# OSO-MISC-20-012_Trinket_SWD_Adapter.net
KiCad netlist of a schematic drawn in EAGLE
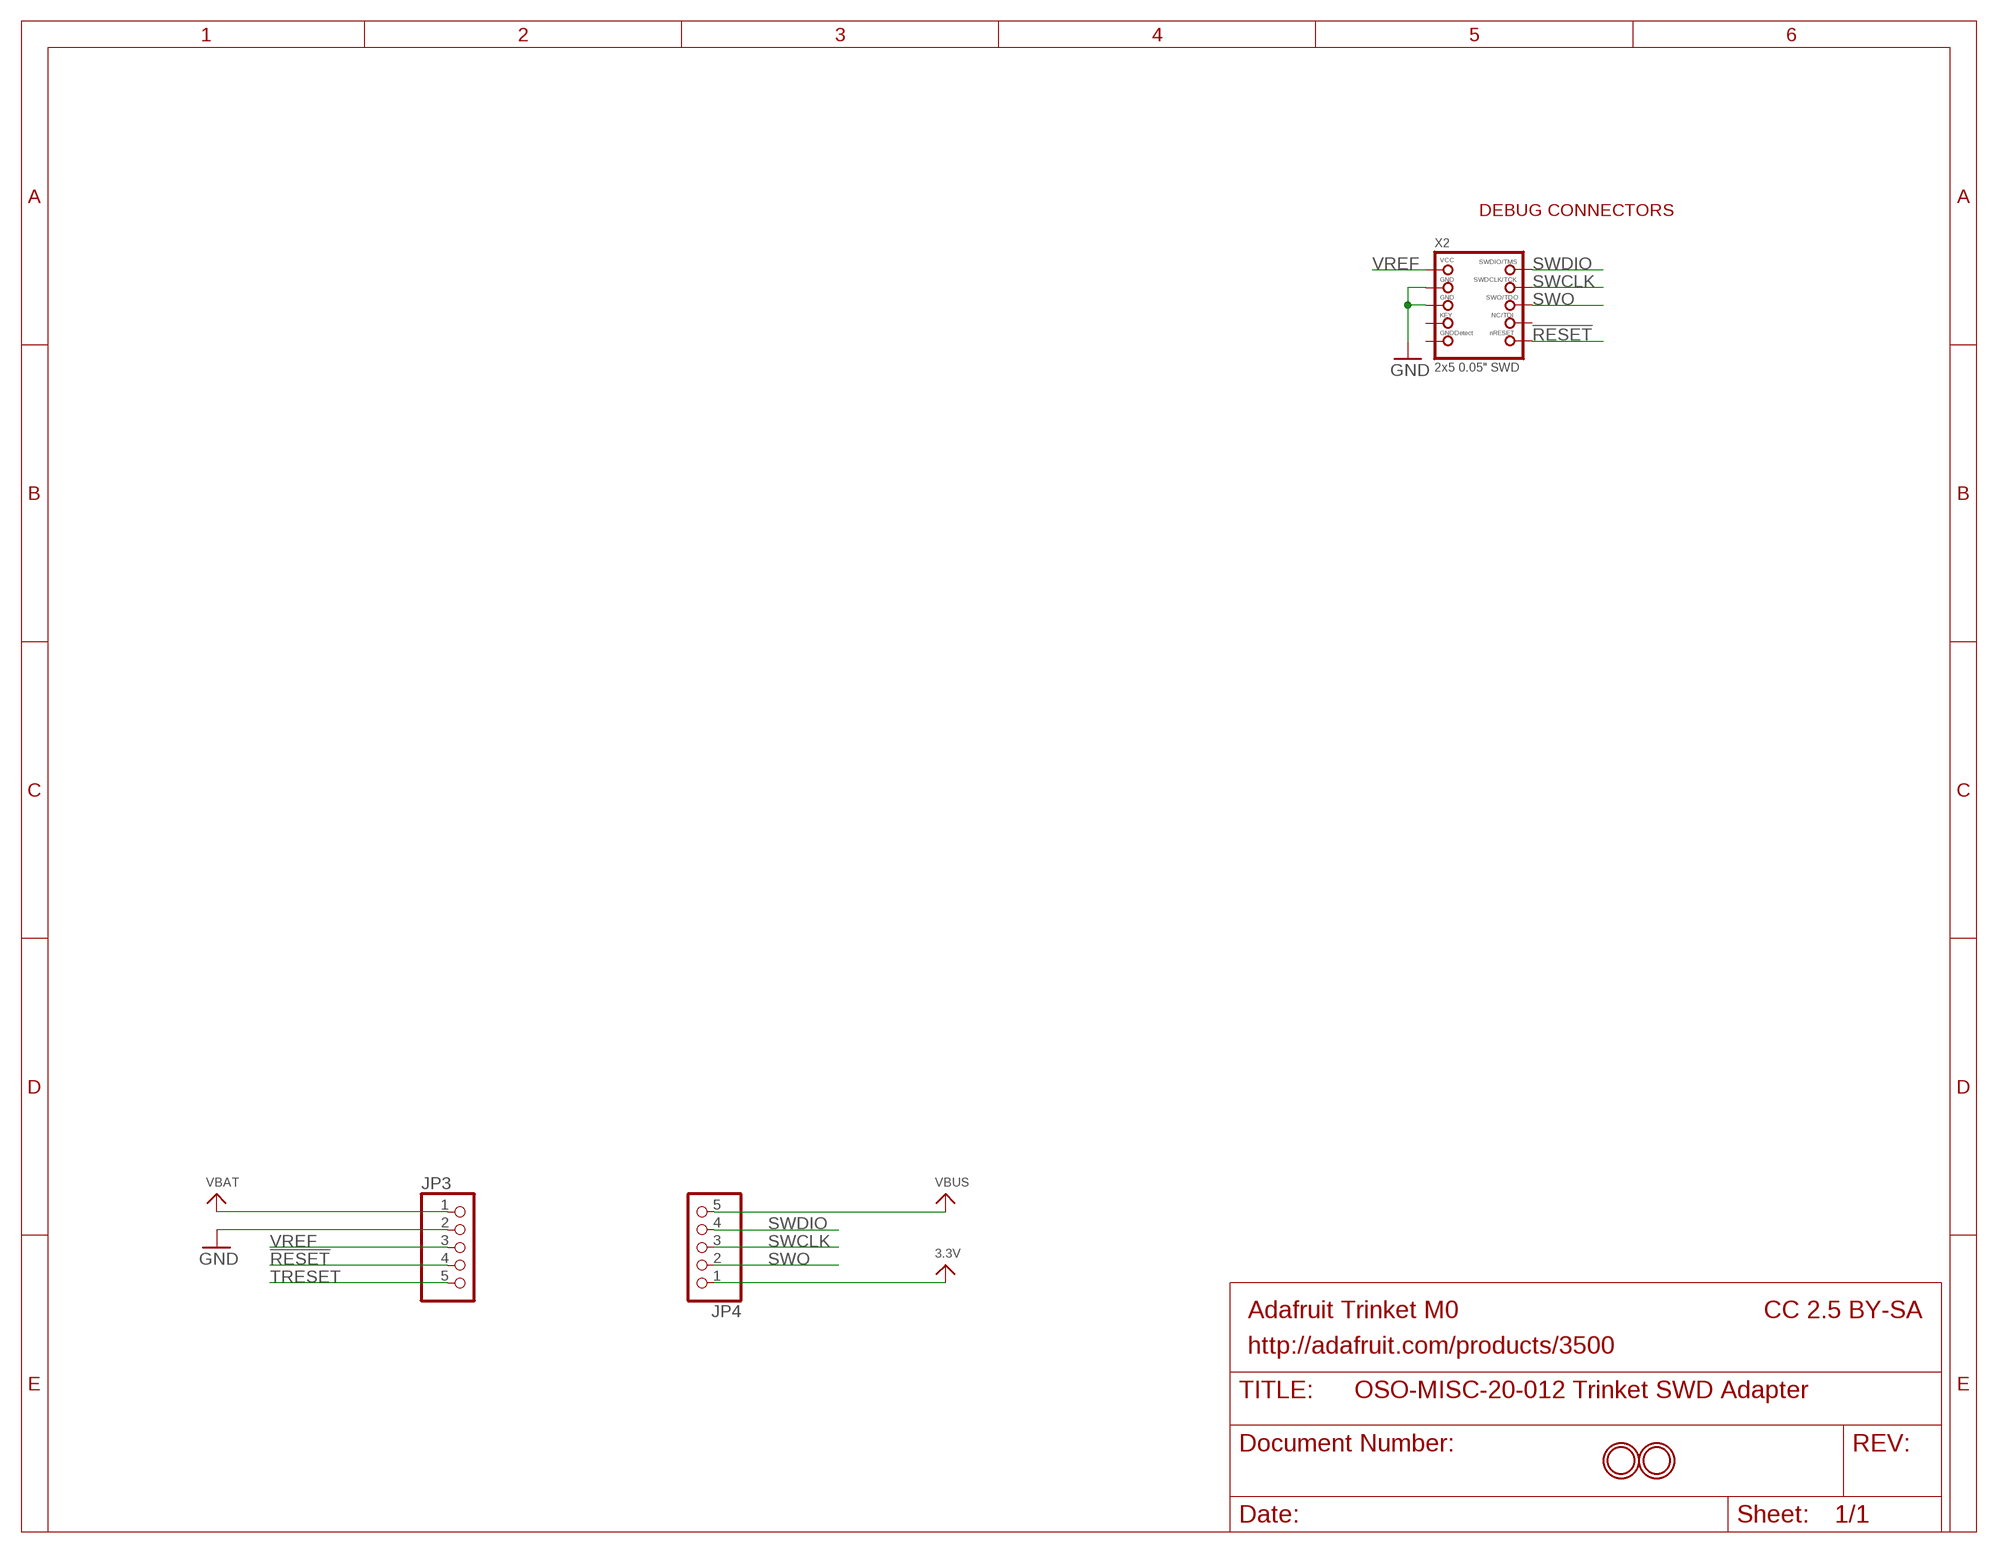
[diagram p0: schematic, sheet 1]

(export (version "E")
  (design (tool "Eeschema 10.0.6"))
  (components
    (comp (ref "JP3")
      (value "HEADER-1X576MIL")
      (footprint "eagle-import:1X05_ROUND_76")
      (libsource (lib "eagle-import") (part "HEADER-1X576MIL"))
    )
    (comp (ref "JP4")
      (value "HEADER-1X576MIL")
      (footprint "eagle-import:1X05_ROUND_76")
      (libsource (lib "eagle-import") (part "HEADER-1X576MIL"))
    )
    (comp (ref "U$8")
      (value "MOUNTINGHOLE2.0")
      (footprint "eagle-import:MOUNTINGHOLE_2.0_PLATED")
      (libsource (lib "eagle-import") (part "MOUNTINGHOLE2.0"))
    )
    (comp (ref "U$9")
      (value "MOUNTINGHOLE2.0")
      (footprint "eagle-import:MOUNTINGHOLE_2.0_PLATED")
      (libsource (lib "eagle-import") (part "MOUNTINGHOLE2.0"))
    )
    (comp (ref "X2")
      (value "2x5 0.05\" SWD")
      (footprint "eagle-import:2X05_1.27MM_BOX_POSTS")
      (libsource (lib "eagle-import") (part "JTAG-CORTEXBOXPOSTS"))
    )
  )
  (nets
    (net (code "1") (name "/SWCLK") (class "Default")
      (node (ref "JP4") (pin "3") (pinfunction "3_3") (pintype "passive"))
      (node (ref "X2") (pin "4") (pinfunction "SWDCLK_4") (pintype "bidirectional"))
    )
    (net (code "2") (name "/SWDIO") (class "Default")
      (node (ref "JP4") (pin "4") (pinfunction "4_4") (pintype "passive"))
      (node (ref "X2") (pin "2") (pinfunction "SWDIO_2") (pintype "bidirectional"))
    )
    (net (code "3") (name "/SWO") (class "Default")
      (node (ref "JP4") (pin "2") (pinfunction "2_2") (pintype "passive"))
      (node (ref "X2") (pin "6") (pinfunction "SWO_6") (pintype "bidirectional"))
    )
    (net (code "4") (name "/TRESET") (class "Default")
      (node (ref "JP3") (pin "5") (pinfunction "5_5") (pintype "passive"))
    )
    (net (code "5") (name "/VREF") (class "Default")
      (node (ref "JP3") (pin "3") (pinfunction "3_3") (pintype "passive"))
      (node (ref "X2") (pin "1") (pinfunction "VCC_1") (pintype "power_in"))
    )
    (net (code "6") (name "/~{RESET}") (class "Default")
      (node (ref "JP3") (pin "4") (pinfunction "4_4") (pintype "passive"))
      (node (ref "X2") (pin "10") (pinfunction "NRESET_10") (pintype "bidirectional"))
    )
    (net (code "7") (name "3.3V") (class "Default")
      (node (ref "JP4") (pin "1") (pinfunction "1_1") (pintype "passive"))
    )
    (net (code "8") (name "GND") (class "Default")
      (node (ref "JP3") (pin "2") (pinfunction "2_2") (pintype "passive"))
      (node (ref "X2") (pin "3") (pinfunction "GND_3") (pintype "power_in"))
      (node (ref "X2") (pin "5") (pinfunction "GND_5") (pintype "power_in"))
    )
    (net (code "9") (name "VBAT") (class "Default")
      (node (ref "JP3") (pin "1") (pinfunction "1_1") (pintype "passive"))
    )
    (net (code "10") (name "VBUS") (class "Default")
      (node (ref "JP4") (pin "5") (pinfunction "5_5") (pintype "passive"))
    )
    (net (code "11") (name "unconnected-(X2-GNDDETECT-Pad9)") (class "Default")
      (node (ref "X2") (pin "9") (pinfunction "GNDDETECT_9") (pintype "bidirectional"))
    )
    (net (code "12") (name "unconnected-(X2-KEY-Pad7)") (class "Default")
      (node (ref "X2") (pin "7") (pinfunction "KEY_7") (pintype "bidirectional"))
    )
    (net (code "13") (name "unconnected-(X2-TDI-Pad8)") (class "Default")
      (node (ref "X2") (pin "8") (pinfunction "TDI_8") (pintype "bidirectional"))
    )
  )
)
